# RS485_IO.net
KiCad netlist of a schematic drawn in Altium Designer
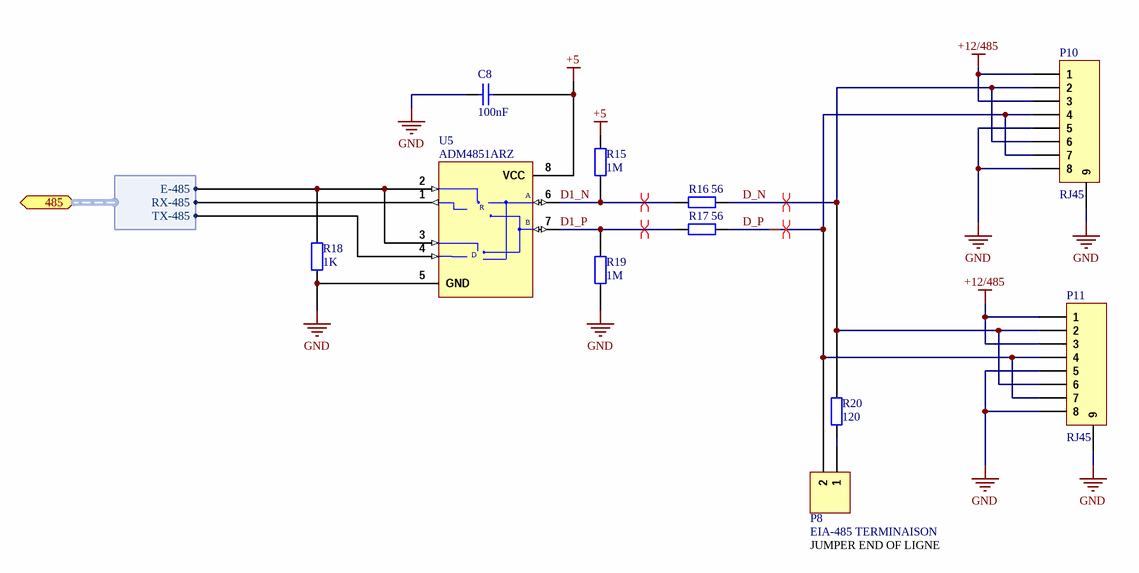
[diagram p0: RS485 IO.SchDoc]

(export (version "E")
  (design (tool "Eeschema 10.0.6"))
  (components
    (comp (ref "C8")
      (value "100nF")
      (footprint "C0805")
      (description "Capacitor")
      (fields
        (field (name "MANUFACTURER") "MULTICOMP")
        (field (name "MANUFACTURER PART NUMBER") "MCCA000296")
      )
      (libsource (lib "BRA") (part "Cap 0805 100nF"))
    )
    (comp (ref "P8")
      (value "EIA-485 TERMINAISON")
      (footprint "M20_1X2")
      (description "Header, 2-Pin")
      (fields
        (field (name "MANUFACTURER") "HARWIN")
        (field (name "MANUFACTURER PART NUMBER") "M20-8770242")
        (field (name "PUBLISHER") "Altium Limited")
      )
      (libsource (lib "Miscellaneous Connectors") (part "Header 2"))
    )
    (comp (ref "P10")
      (value "RJ45")
      (footprint "AMPHENOL-RJ45_8")
      (description "Header, 8-Pin")
      (fields
        (field (name "MANUFACTURER") "MOLEX")
        (field (name "MANUFACTURER PART NUMBER") "85513-5013")
        (field (name "APPROVAL CATEGORY") "UL 94V-0")
        (field (name "LONGUEUR/HAUTEUR") "13")
      )
      (libsource (lib "MAIN BOARD CERES") (part "Header 8"))
    )
    (comp (ref "P11")
      (value "RJ45")
      (footprint "AMPHENOL-RJ45_8")
      (description "Header, 8-Pin")
      (fields
        (field (name "MANUFACTURER") "MOLEX")
        (field (name "MANUFACTURER PART NUMBER") "85513-5013")
        (field (name "APPROVAL CATEGORY") "UL 94V-0")
        (field (name "LONGUEUR/HAUTEUR") "13")
      )
      (libsource (lib "MAIN BOARD CERES") (part "Header 8"))
    )
    (comp (ref "R15")
      (value "1M")
      (footprint "R0805")
      (description "Resistor")
      (libsource (lib "BRA") (part "Resistor 0805 1M"))
    )
    (comp (ref "R16")
      (value "56")
      (footprint "R0805")
      (description "Resistor")
      (fields
        (field (name "MANUFACTURER") "MULTICOMP")
        (field (name "MANUFACTURER PART NUMBER") "MC01W0805156R")
      )
      (libsource (lib "BRA") (part "Resistor 0805 56"))
    )
    (comp (ref "R17")
      (value "56")
      (footprint "R0805")
      (description "Resistor")
      (fields
        (field (name "MANUFACTURER") "MULTICOMP")
        (field (name "MANUFACTURER PART NUMBER") "MC01W0805156R")
      )
      (libsource (lib "BRA") (part "Resistor 0805 56"))
    )
    (comp (ref "R18")
      (value "1K")
      (footprint "R0805")
      (description "Resistor")
      (fields
        (field (name "MANUFACTURER") "MULTICOMP")
        (field (name "MANUFACTURER PART NUMBER") "MC0.1W08051%1KFR")
      )
      (libsource (lib "BRA") (part "Resistor 0805 1K"))
    )
    (comp (ref "R19")
      (value "1M")
      (footprint "R0805")
      (description "Resistor")
      (libsource (lib "BRA") (part "Resistor 0805 1M"))
    )
    (comp (ref "R20")
      (value "120")
      (footprint "R0805")
      (description "Resistor")
      (fields
        (field (name "MANUFACTURER") "MULTICOMP")
        (field (name "MANUFACTURER PART NUMBER") "MC01W080516K49")
      )
      (libsource (lib "BRA") (part "Resistor 0805 120"))
    )
    (comp (ref "U5")
      (value "ADM4851ARZ")
      (footprint "SOIC8")
      (description "Low-Power, Slew-Rate-Limited RS-485/RS-422 Transceiver")
      (fields (field (name "MANUFACTURER") "ANALOG DEVICES"))
      (libsource (lib "Maxim Communication Transceiver") (part "MAX485ESA"))
    )
  )
  (nets
    (net (code "2") (name "+5") (class "Default")
      (node (ref "C8") (pin "1") (pinfunction "1_1") (pintype "passive"))
      (node (ref "R15") (pin "2") (pinfunction "2_2") (pintype "passive"))
      (node (ref "U5") (pin "8") (pinfunction "VCC_8") (pintype "power_in"))
    )
    (net (code "3") (name "+12{slash}485") (class "Default")
      (node (ref "P10") (pin "1") (pinfunction "1_1") (pintype "passive"))
      (node (ref "P10") (pin "3") (pinfunction "3_3") (pintype "passive"))
      (node (ref "P11") (pin "1") (pinfunction "1_1") (pintype "passive"))
      (node (ref "P11") (pin "3") (pinfunction "3_3") (pintype "passive"))
    )
    (net (code "4") (name "/D1_N") (class "Default")
      (node (ref "R15") (pin "1") (pinfunction "1_1") (pintype "passive"))
      (node (ref "R16") (pin "1") (pinfunction "1_1") (pintype "passive"))
      (node (ref "U5") (pin "6") (pinfunction "A_6") (pintype "bidirectional"))
    )
    (net (code "5") (name "/D1_P") (class "Default")
      (node (ref "R17") (pin "1") (pinfunction "1_1") (pintype "passive"))
      (node (ref "R19") (pin "2") (pinfunction "2_2") (pintype "passive"))
      (node (ref "U5") (pin "7") (pinfunction "B_7") (pintype "bidirectional"))
    )
    (net (code "6") (name "/D_N") (class "Default")
      (node (ref "P10") (pin "2") (pinfunction "2_2") (pintype "passive"))
      (node (ref "P10") (pin "6") (pinfunction "6_6") (pintype "passive"))
      (node (ref "P11") (pin "2") (pinfunction "2_2") (pintype "passive"))
      (node (ref "P11") (pin "6") (pinfunction "6_6") (pintype "passive"))
      (node (ref "R16") (pin "2") (pinfunction "2_2") (pintype "passive"))
      (node (ref "R20") (pin "2") (pinfunction "2_2") (pintype "passive"))
    )
    (net (code "7") (name "/D_P") (class "Default")
      (node (ref "P10") (pin "4") (pinfunction "4_4") (pintype "passive"))
      (node (ref "P10") (pin "7") (pinfunction "7_7") (pintype "passive"))
      (node (ref "P11") (pin "4") (pinfunction "4_4") (pintype "passive"))
      (node (ref "P11") (pin "7") (pinfunction "7_7") (pintype "passive"))
      (node (ref "P8") (pin "2") (pinfunction "2_2") (pintype "passive"))
      (node (ref "R17") (pin "2") (pinfunction "2_2") (pintype "passive"))
    )
    (net (code "8") (name "/E-485") (class "Default")
      (node (ref "R18") (pin "2") (pinfunction "2_2") (pintype "passive"))
      (node (ref "U5") (pin "2") (pinfunction "~{RE}_2") (pintype "input"))
      (node (ref "U5") (pin "3") (pinfunction "DE_3") (pintype "input"))
    )
    (net (code "9") (name "/RX-485") (class "Default")
      (node (ref "U5") (pin "1") (pinfunction "RO_1") (pintype "output"))
    )
    (net (code "10") (name "/TX-485") (class "Default")
      (node (ref "U5") (pin "4") (pinfunction "DI_4") (pintype "input"))
    )
    (net (code "12") (name "GND") (class "Default")
      (node (ref "C8") (pin "2") (pinfunction "2_2") (pintype "passive"))
      (node (ref "P10") (pin "5") (pinfunction "5_5") (pintype "passive"))
      (node (ref "P10") (pin "8") (pinfunction "8_8") (pintype "passive"))
      (node (ref "P10") (pin "9") (pinfunction "9_9") (pintype "passive"))
      (node (ref "P11") (pin "5") (pinfunction "5_5") (pintype "passive"))
      (node (ref "P11") (pin "8") (pinfunction "8_8") (pintype "passive"))
      (node (ref "P11") (pin "9") (pinfunction "9_9") (pintype "passive"))
      (node (ref "R18") (pin "1") (pinfunction "1_1") (pintype "passive"))
      (node (ref "R19") (pin "1") (pinfunction "1_1") (pintype "passive"))
      (node (ref "U5") (pin "5") (pinfunction "GND_5") (pintype "power_in"))
    )
    (net (code "13") (name "Net-(P8-Pad1)") (class "Default")
      (node (ref "P8") (pin "1") (pinfunction "1_1") (pintype "passive"))
      (node (ref "R20") (pin "1") (pinfunction "1_1") (pintype "passive"))
    )
  )
)
